# 433_1.net
KiCad netlist of a schematic drawn in EAGLE
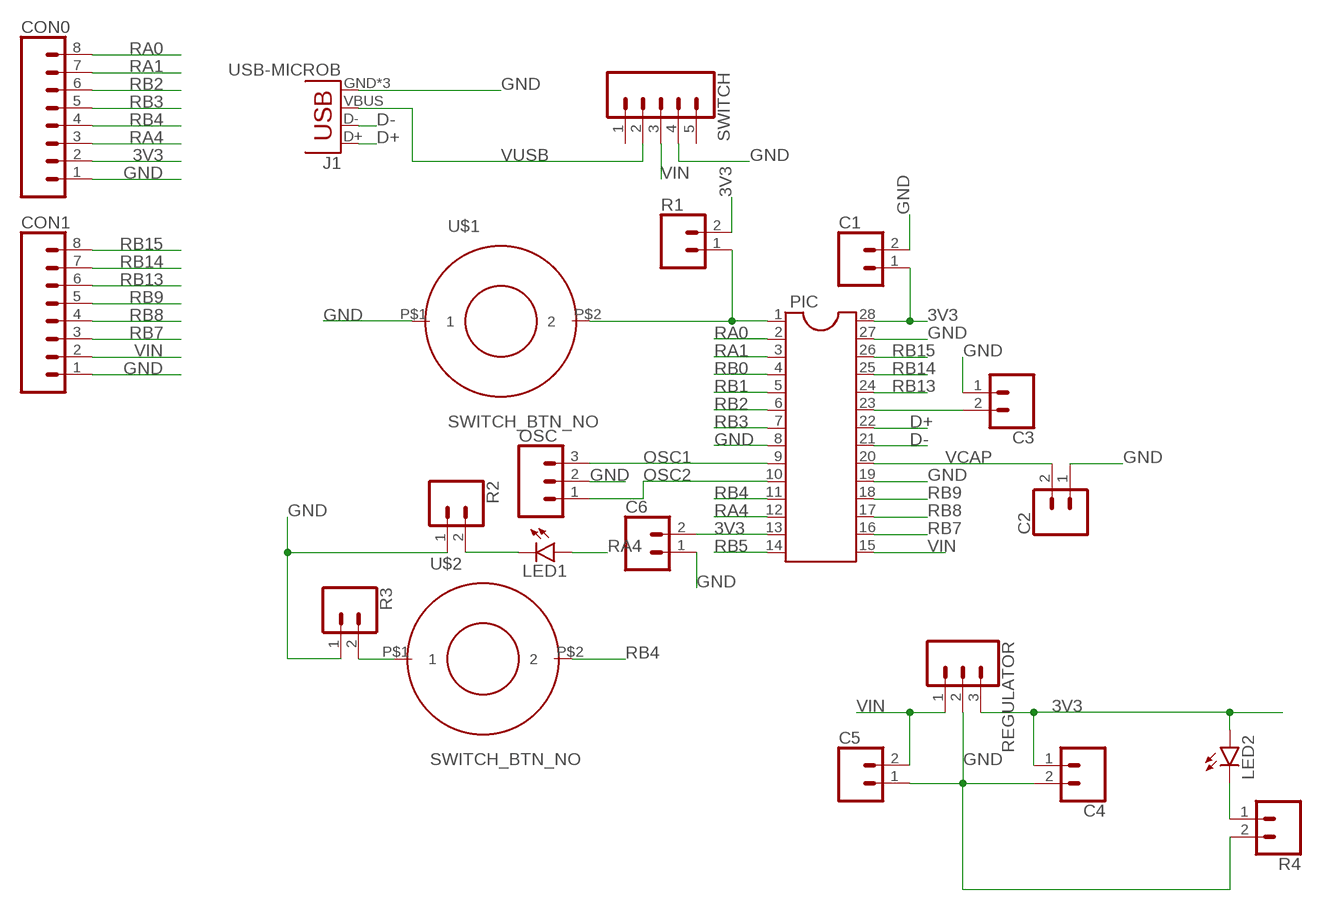
[diagram p0: schematic, sheet 1]

(export (version "E")
  (design (tool "Eeschema 10.0.6"))
  (components
    (comp (ref "C1")
      (value "CONN_02")
      (footprint "eagle-import:1X02")
      (libsource (lib "eagle-import") (part "CONN_02"))
    )
    (comp (ref "C2")
      (value "CONN_02")
      (footprint "eagle-import:1X02")
      (libsource (lib "eagle-import") (part "CONN_02"))
    )
    (comp (ref "C3")
      (value "CONN_02")
      (footprint "eagle-import:1X02")
      (libsource (lib "eagle-import") (part "CONN_02"))
    )
    (comp (ref "C4")
      (value "CONN_02")
      (footprint "eagle-import:1X02")
      (libsource (lib "eagle-import") (part "CONN_02"))
    )
    (comp (ref "C5")
      (value "CONN_02")
      (footprint "eagle-import:1X02")
      (libsource (lib "eagle-import") (part "CONN_02"))
    )
    (comp (ref "C6")
      (value "CONN_02")
      (footprint "eagle-import:1X02")
      (libsource (lib "eagle-import") (part "CONN_02"))
    )
    (comp (ref "CON0")
      (value "CONN_08\"")
      (footprint "eagle-import:1X08")
      (libsource (lib "eagle-import") (part "CONN_08{dblquote}"))
    )
    (comp (ref "CON1")
      (value "CONN_08\"")
      (footprint "eagle-import:1X08")
      (libsource (lib "eagle-import") (part "CONN_08{dblquote}"))
    )
    (comp (ref "J1")
      (value "USB-MICROB")
      (footprint "eagle-import:USB-MICROB")
      (libsource (lib "eagle-import") (part "USB-MICROB"))
    )
    (comp (ref "LED1")
      (value "LED3MM")
      (footprint "eagle-import:LED3MM")
      (libsource (lib "eagle-import") (part "LED3MM"))
    )
    (comp (ref "LED2")
      (value "LED3MM")
      (footprint "eagle-import:LED3MM")
      (libsource (lib "eagle-import") (part "LED3MM"))
    )
    (comp (ref "OSC")
      (value "CONN_03")
      (footprint "eagle-import:1X03")
      (libsource (lib "eagle-import") (part "CONN_03"))
    )
    (comp (ref "PIC")
      (value "DIL28-4")
      (footprint "eagle-import:DIL28-4")
      (libsource (lib "eagle-import") (part "DIL28-4"))
    )
    (comp (ref "R1")
      (value "CONN_02")
      (footprint "eagle-import:1X02")
      (libsource (lib "eagle-import") (part "CONN_02"))
    )
    (comp (ref "R2")
      (value "CONN_02")
      (footprint "eagle-import:1X02")
      (libsource (lib "eagle-import") (part "CONN_02"))
    )
    (comp (ref "R3")
      (value "CONN_02")
      (footprint "eagle-import:1X02")
      (libsource (lib "eagle-import") (part "CONN_02"))
    )
    (comp (ref "R4")
      (value "CONN_02")
      (footprint "eagle-import:1X02")
      (libsource (lib "eagle-import") (part "CONN_02"))
    )
    (comp (ref "REGULATOR")
      (value "CONN_03")
      (footprint "eagle-import:1X03")
      (libsource (lib "eagle-import") (part "CONN_03"))
    )
    (comp (ref "SWITCH")
      (value "CONN_05")
      (footprint "eagle-import:1X05")
      (libsource (lib "eagle-import") (part "CONN_05"))
    )
    (comp (ref "U$1")
      (value "SWITCH_BTN_NO")
      (footprint "eagle-import:BTN_2")
      (libsource (lib "eagle-import") (part "SWITCH_BTN_NO"))
    )
    (comp (ref "U$2")
      (value "SWITCH_BTN_NO")
      (footprint "eagle-import:BTN_2")
      (libsource (lib "eagle-import") (part "SWITCH_BTN_NO"))
    )
  )
  (nets
    (net (code "1") (name "/3V3") (class "Default")
      (node (ref "C1") (pin "1") (pinfunction "1_1") (pintype "passive"))
      (node (ref "C3") (pin "2") (pinfunction "2_2") (pintype "passive"))
      (node (ref "C4") (pin "1") (pinfunction "1_1") (pintype "passive"))
      (node (ref "C6") (pin "2") (pinfunction "2_2") (pintype "passive"))
      (node (ref "CON0") (pin "2") (pinfunction "2_2") (pintype "passive"))
      (node (ref "LED2") (pin "A") (pinfunction "A_A") (pintype "passive"))
      (node (ref "PIC") (pin "13") (pinfunction "13_13") (pintype "passive"))
      (node (ref "PIC") (pin "23") (pinfunction "23_23") (pintype "passive"))
      (node (ref "PIC") (pin "28") (pinfunction "28_28") (pintype "passive"))
      (node (ref "R1") (pin "2") (pinfunction "2_2") (pintype "passive"))
      (node (ref "REGULATOR") (pin "3") (pinfunction "3_3") (pintype "passive"))
    )
    (net (code "2") (name "/D+") (class "Default")
      (node (ref "J1") (pin "D+") (pinfunction "D+_D+") (pintype "bidirectional"))
      (node (ref "PIC") (pin "22") (pinfunction "22_22") (pintype "passive"))
    )
    (net (code "3") (name "/D-") (class "Default")
      (node (ref "J1") (pin "D-") (pinfunction "D-_D-") (pintype "bidirectional"))
      (node (ref "PIC") (pin "21") (pinfunction "21_21") (pintype "passive"))
    )
    (net (code "4") (name "/GND") (class "Default")
      (node (ref "C1") (pin "2") (pinfunction "2_2") (pintype "passive"))
      (node (ref "C2") (pin "1") (pinfunction "1_1") (pintype "passive"))
      (node (ref "C3") (pin "1") (pinfunction "1_1") (pintype "passive"))
      (node (ref "C4") (pin "2") (pinfunction "2_2") (pintype "passive"))
      (node (ref "C5") (pin "1") (pinfunction "1_1") (pintype "passive"))
      (node (ref "C6") (pin "1") (pinfunction "1_1") (pintype "passive"))
      (node (ref "CON0") (pin "1") (pinfunction "1_1") (pintype "passive"))
      (node (ref "CON1") (pin "1") (pinfunction "1_1") (pintype "passive"))
      (node (ref "J1") (pin "GND") (pinfunction "GND_GND") (pintype "bidirectional"))
      (node (ref "J1") (pin "MT1") (pinfunction "GND_MT1") (pintype "bidirectional"))
      (node (ref "J1") (pin "MT2") (pinfunction "GND_MT2") (pintype "bidirectional"))
      (node (ref "OSC") (pin "2") (pinfunction "2_2") (pintype "passive"))
      (node (ref "PIC") (pin "19") (pinfunction "19_19") (pintype "passive"))
      (node (ref "PIC") (pin "27") (pinfunction "27_27") (pintype "passive"))
      (node (ref "PIC") (pin "8") (pinfunction "8_8") (pintype "passive"))
      (node (ref "R2") (pin "1") (pinfunction "1_1") (pintype "passive"))
      (node (ref "R3") (pin "1") (pinfunction "1_1") (pintype "passive"))
      (node (ref "R4") (pin "2") (pinfunction "2_2") (pintype "passive"))
      (node (ref "REGULATOR") (pin "2") (pinfunction "2_2") (pintype "passive"))
      (node (ref "SWITCH") (pin "4") (pinfunction "4_4") (pintype "passive"))
      (node (ref "U$1") (pin "P$1") (pinfunction "1_P$1") (pintype "bidirectional"))
    )
    (net (code "5") (name "/OSC1") (class "Default")
      (node (ref "OSC") (pin "3") (pinfunction "3_3") (pintype "passive"))
      (node (ref "PIC") (pin "9") (pinfunction "9_9") (pintype "passive"))
    )
    (net (code "6") (name "/OSC2") (class "Default")
      (node (ref "OSC") (pin "1") (pinfunction "1_1") (pintype "passive"))
      (node (ref "PIC") (pin "10") (pinfunction "10_10") (pintype "passive"))
    )
    (net (code "7") (name "/RA0") (class "Default")
      (node (ref "CON0") (pin "8") (pinfunction "8_8") (pintype "passive"))
      (node (ref "PIC") (pin "2") (pinfunction "2_2") (pintype "passive"))
    )
    (net (code "8") (name "/RA1") (class "Default")
      (node (ref "CON0") (pin "7") (pinfunction "7_7") (pintype "passive"))
      (node (ref "PIC") (pin "3") (pinfunction "3_3") (pintype "passive"))
    )
    (net (code "9") (name "/RA4") (class "Default")
      (node (ref "CON0") (pin "3") (pinfunction "3_3") (pintype "passive"))
      (node (ref "LED1") (pin "A") (pinfunction "A_A") (pintype "passive"))
      (node (ref "PIC") (pin "12") (pinfunction "12_12") (pintype "passive"))
    )
    (net (code "10") (name "/RB0") (class "Default")
      (node (ref "PIC") (pin "4") (pinfunction "4_4") (pintype "passive"))
    )
    (net (code "11") (name "/RB1") (class "Default")
      (node (ref "PIC") (pin "5") (pinfunction "5_5") (pintype "passive"))
    )
    (net (code "12") (name "/RB2") (class "Default")
      (node (ref "CON0") (pin "6") (pinfunction "6_6") (pintype "passive"))
      (node (ref "PIC") (pin "6") (pinfunction "6_6") (pintype "passive"))
    )
    (net (code "13") (name "/RB3") (class "Default")
      (node (ref "CON0") (pin "5") (pinfunction "5_5") (pintype "passive"))
      (node (ref "PIC") (pin "7") (pinfunction "7_7") (pintype "passive"))
    )
    (net (code "14") (name "/RB4") (class "Default")
      (node (ref "CON0") (pin "4") (pinfunction "4_4") (pintype "passive"))
      (node (ref "PIC") (pin "11") (pinfunction "11_11") (pintype "passive"))
      (node (ref "U$2") (pin "P$2") (pinfunction "2_P$2") (pintype "bidirectional"))
    )
    (net (code "15") (name "/RB5") (class "Default")
      (node (ref "PIC") (pin "14") (pinfunction "14_14") (pintype "passive"))
    )
    (net (code "16") (name "/RB7") (class "Default")
      (node (ref "CON1") (pin "3") (pinfunction "3_3") (pintype "passive"))
      (node (ref "PIC") (pin "16") (pinfunction "16_16") (pintype "passive"))
    )
    (net (code "17") (name "/RB8") (class "Default")
      (node (ref "CON1") (pin "4") (pinfunction "4_4") (pintype "passive"))
      (node (ref "PIC") (pin "17") (pinfunction "17_17") (pintype "passive"))
    )
    (net (code "18") (name "/RB9") (class "Default")
      (node (ref "CON1") (pin "5") (pinfunction "5_5") (pintype "passive"))
      (node (ref "PIC") (pin "18") (pinfunction "18_18") (pintype "passive"))
    )
    (net (code "19") (name "/RB13") (class "Default")
      (node (ref "CON1") (pin "6") (pinfunction "6_6") (pintype "passive"))
      (node (ref "PIC") (pin "24") (pinfunction "24_24") (pintype "passive"))
    )
    (net (code "20") (name "/RB14") (class "Default")
      (node (ref "CON1") (pin "7") (pinfunction "7_7") (pintype "passive"))
      (node (ref "PIC") (pin "25") (pinfunction "25_25") (pintype "passive"))
    )
    (net (code "21") (name "/RB15") (class "Default")
      (node (ref "CON1") (pin "8") (pinfunction "8_8") (pintype "passive"))
      (node (ref "PIC") (pin "26") (pinfunction "26_26") (pintype "passive"))
    )
    (net (code "22") (name "/VCAP") (class "Default")
      (node (ref "C2") (pin "2") (pinfunction "2_2") (pintype "passive"))
      (node (ref "PIC") (pin "20") (pinfunction "20_20") (pintype "passive"))
    )
    (net (code "23") (name "/VIN") (class "Default")
      (node (ref "C5") (pin "2") (pinfunction "2_2") (pintype "passive"))
      (node (ref "CON1") (pin "2") (pinfunction "2_2") (pintype "passive"))
      (node (ref "PIC") (pin "15") (pinfunction "15_15") (pintype "passive"))
      (node (ref "REGULATOR") (pin "1") (pinfunction "1_1") (pintype "passive"))
      (node (ref "SWITCH") (pin "3") (pinfunction "3_3") (pintype "passive"))
    )
    (net (code "24") (name "/VUSB") (class "Default")
      (node (ref "J1") (pin "VBUS") (pinfunction "VBUS_VBUS") (pintype "bidirectional"))
      (node (ref "SWITCH") (pin "2") (pinfunction "2_2") (pintype "passive"))
    )
    (net (code "25") (name "Net-(LED1-C)") (class "Default")
      (node (ref "LED1") (pin "K") (pinfunction "C_K") (pintype "passive"))
      (node (ref "R2") (pin "2") (pinfunction "2_2") (pintype "passive"))
    )
    (net (code "26") (name "Net-(LED2-C)") (class "Default")
      (node (ref "LED2") (pin "K") (pinfunction "C_K") (pintype "passive"))
      (node (ref "R4") (pin "1") (pinfunction "1_1") (pintype "passive"))
    )
    (net (code "27") (name "Net-(U$1-2)") (class "Default")
      (node (ref "PIC") (pin "1") (pinfunction "1_1") (pintype "passive"))
      (node (ref "R1") (pin "1") (pinfunction "1_1") (pintype "passive"))
      (node (ref "U$1") (pin "P$2") (pinfunction "2_P$2") (pintype "bidirectional"))
    )
    (net (code "28") (name "Net-(U$2-1)") (class "Default")
      (node (ref "R3") (pin "2") (pinfunction "2_2") (pintype "passive"))
      (node (ref "U$2") (pin "P$1") (pinfunction "1_P$1") (pintype "bidirectional"))
    )
    (net (code "29") (name "unconnected-(SWITCH-Pad1)") (class "Default")
      (node (ref "SWITCH") (pin "1") (pinfunction "1_1") (pintype "passive"))
    )
    (net (code "30") (name "unconnected-(SWITCH-Pad5)") (class "Default")
      (node (ref "SWITCH") (pin "5") (pinfunction "5_5") (pintype "passive"))
    )
  )
)
